# Display_EUA.net
KiCad netlist of a schematic drawn in Altium Designer
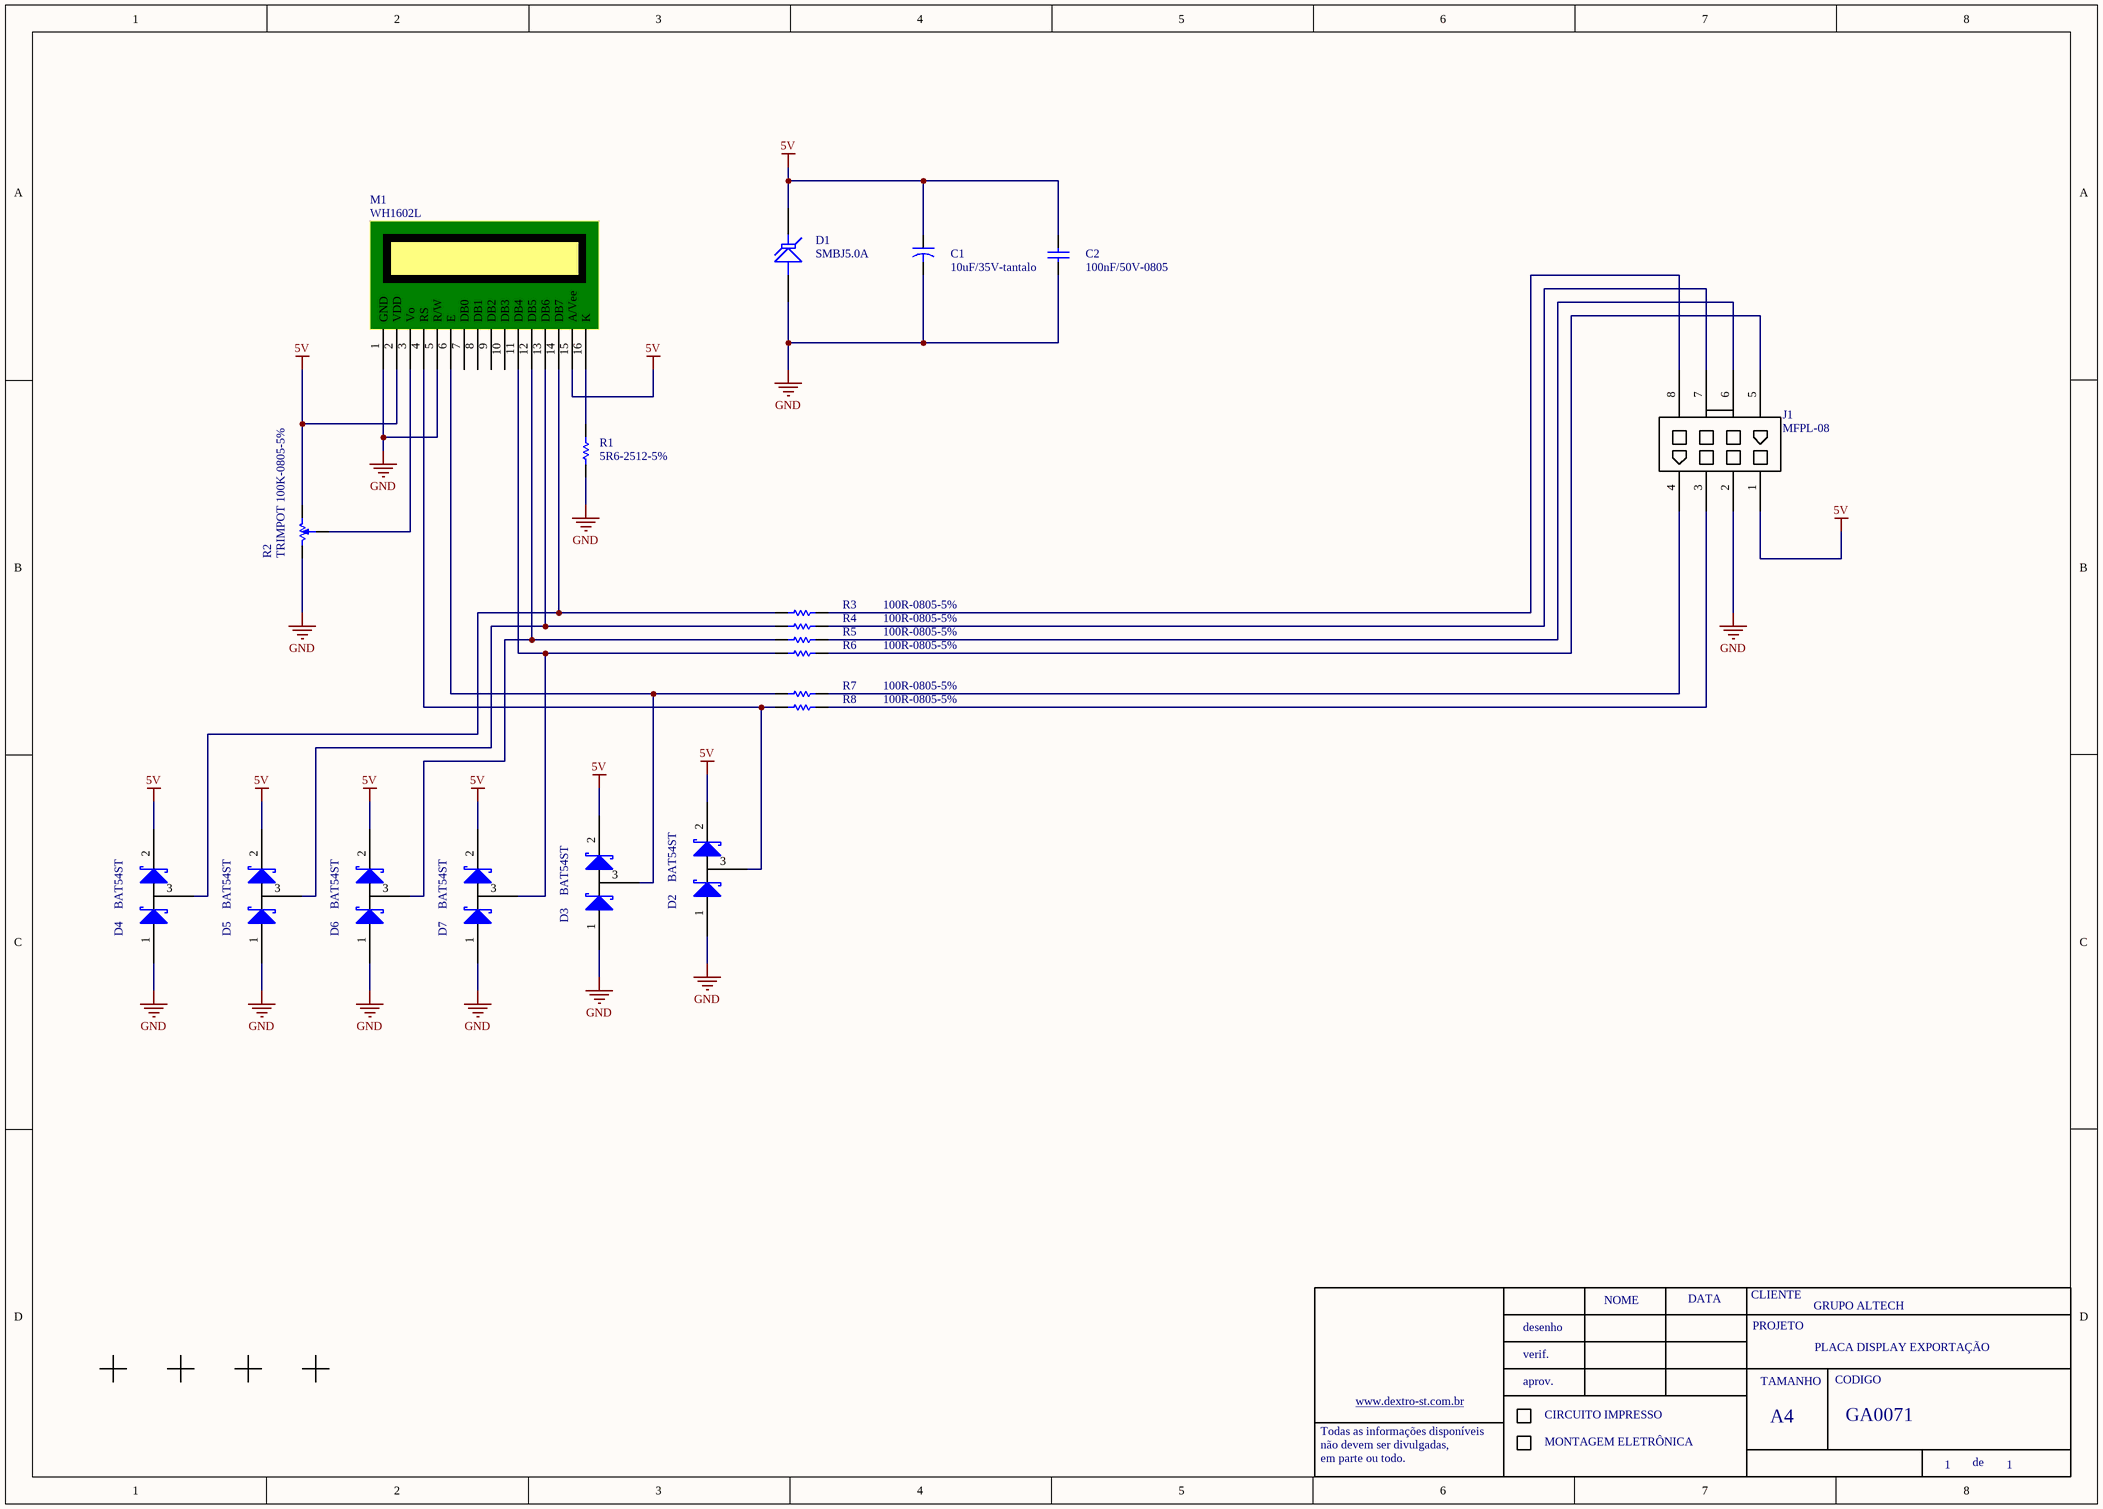
[diagram p0: Display_EUA.SchDoc]

(export (version "E")
  (design (tool "Eeschema 10.0.6"))
  (components
    (comp (ref "C1")
      (value "10uF/35V-tantalo")
      (footprint "tantalo vishay E")
      (libsource (lib "AquinoLib") (part "10uF/35V-tantalo"))
    )
    (comp (ref "C2")
      (value "100nF/50V-0805")
      (footprint "0805-REVISADO ONDA")
      (libsource (lib "AquinoLib") (part "100nF/50-0805-NPO"))
    )
    (comp (ref "D1")
      (value "SMBJ5.0A")
      (footprint "DO-214AA")
      (libsource (lib "AquinoLib") (part "SMBJ5.0A"))
    )
    (comp (ref "D2")
      (value "BAT54ST")
      (footprint "SOT23 - REVISADO ONDA")
      (libsource (lib "AquinoLib") (part "BAT54ST"))
    )
    (comp (ref "D3")
      (value "BAT54ST")
      (footprint "SOT23 - REVISADO ONDA")
      (libsource (lib "AquinoLib") (part "BAT54ST"))
    )
    (comp (ref "D4")
      (value "BAT54ST")
      (footprint "SOT23 - REVISADO ONDA")
      (libsource (lib "AquinoLib") (part "BAT54ST"))
    )
    (comp (ref "D5")
      (value "BAT54ST")
      (footprint "SOT23 - REVISADO ONDA")
      (libsource (lib "AquinoLib") (part "BAT54ST"))
    )
    (comp (ref "D6")
      (value "BAT54ST")
      (footprint "SOT23 - REVISADO ONDA")
      (libsource (lib "AquinoLib") (part "BAT54ST"))
    )
    (comp (ref "D7")
      (value "BAT54ST")
      (footprint "SOT23 - REVISADO ONDA")
      (libsource (lib "AquinoLib") (part "BAT54ST"))
    )
    (comp (ref "FD1")
      (value "FID")
      (footprint "FIDUCIAL CRUZ")
      (libsource (lib "ChaveDigital3") (part "FIDUCIAL"))
    )
    (comp (ref "FD2")
      (value "FID")
      (footprint "FIDUCIAL CRUZ")
      (libsource (lib "ChaveDigital3") (part "FIDUCIAL"))
    )
    (comp (ref "FD3")
      (value "FID")
      (footprint "FIDUCIAL CRUZ")
      (libsource (lib "ChaveDigital3") (part "FIDUCIAL"))
    )
    (comp (ref "FD4")
      (value "FID")
      (footprint "FIDUCIAL CRUZ")
      (libsource (lib "ChaveDigital3") (part "FIDUCIAL"))
    )
    (comp (ref "J1") (value "MFPL-08") (footprint "MFPC-08") (libsource (lib "AquinoLib") (part "MFPL-08")))
    (comp (ref "M1") (value "WH1602L") (footprint "WH1602L1") (libsource (lib "AquinoLib") (part "WH1602L")))
    (comp (ref "R1")
      (value "5R6-2512-5%")
      (footprint "2512 - REVISADO ONDA")
      (libsource (lib "AquinoLib") (part "5R6-2512-1%"))
    )
    (comp (ref "R2")
      (value "TRIMPOT 100K-0805-5%")
      (footprint "trimmer 3386")
      (libsource (lib "AquinoLib") (part "TRIMPOT 10K-3386"))
    )
    (comp (ref "R3")
      (value "100R-0805-5%")
      (footprint "0805-REVISADO ONDA")
      (libsource (lib "AquinoLib") (part "100R-0805-5%"))
    )
    (comp (ref "R4")
      (value "100R-0805-5%")
      (footprint "0805-REVISADO ONDA")
      (libsource (lib "AquinoLib") (part "100R-0805-5%"))
    )
    (comp (ref "R5")
      (value "100R-0805-5%")
      (footprint "0805-REVISADO ONDA")
      (libsource (lib "AquinoLib") (part "100R-0805-5%"))
    )
    (comp (ref "R6")
      (value "100R-0805-5%")
      (footprint "0805-REVISADO ONDA")
      (libsource (lib "AquinoLib") (part "100R-0805-5%"))
    )
    (comp (ref "R7")
      (value "100R-0805-5%")
      (footprint "0805-REVISADO ONDA")
      (libsource (lib "AquinoLib") (part "100R-0805-5%"))
    )
    (comp (ref "R8")
      (value "100R-0805-5%")
      (footprint "0805-REVISADO ONDA")
      (libsource (lib "AquinoLib") (part "100R-0805-5%"))
    )
  )
  (nets
    (net (code "1") (name "5V") (class "Default")
      (node (ref "C1") (pin "1") (pinfunction "1_1") (pintype "passive"))
      (node (ref "C2") (pin "2") (pinfunction "2_2") (pintype "passive"))
      (node (ref "D1") (pin "2") (pinfunction "K_2") (pintype "passive"))
      (node (ref "D2") (pin "2") (pinfunction "2_2") (pintype "passive"))
      (node (ref "D3") (pin "2") (pinfunction "2_2") (pintype "passive"))
      (node (ref "D4") (pin "2") (pinfunction "2_2") (pintype "passive"))
      (node (ref "D5") (pin "2") (pinfunction "2_2") (pintype "passive"))
      (node (ref "D6") (pin "2") (pinfunction "2_2") (pintype "passive"))
      (node (ref "D7") (pin "2") (pinfunction "2_2") (pintype "passive"))
      (node (ref "J1") (pin "1") (pinfunction "1_1") (pintype "passive"))
      (node (ref "M1") (pin "15") (pinfunction "A/Vee_15") (pintype "passive"))
      (node (ref "M1") (pin "2") (pinfunction "VDD_2") (pintype "passive"))
      (node (ref "R2") (pin "3") (pinfunction "3_3") (pintype "passive"))
    )
    (net (code "2") (name "GND") (class "Default")
      (node (ref "C1") (pin "2") (pinfunction "2_2") (pintype "passive"))
      (node (ref "C2") (pin "1") (pinfunction "1_1") (pintype "passive"))
      (node (ref "D1") (pin "1") (pinfunction "A_1") (pintype "passive"))
      (node (ref "D2") (pin "1") (pinfunction "1_1") (pintype "passive"))
      (node (ref "D3") (pin "1") (pinfunction "1_1") (pintype "passive"))
      (node (ref "D4") (pin "1") (pinfunction "1_1") (pintype "passive"))
      (node (ref "D5") (pin "1") (pinfunction "1_1") (pintype "passive"))
      (node (ref "D6") (pin "1") (pinfunction "1_1") (pintype "passive"))
      (node (ref "D7") (pin "1") (pinfunction "1_1") (pintype "passive"))
      (node (ref "J1") (pin "2") (pinfunction "2_2") (pintype "passive"))
      (node (ref "M1") (pin "1") (pinfunction "GND_1") (pintype "passive"))
      (node (ref "M1") (pin "5") (pinfunction "R/W_5") (pintype "passive"))
      (node (ref "R1") (pin "1") (pinfunction "1_1") (pintype "passive"))
      (node (ref "R2") (pin "1") (pinfunction "1_1") (pintype "passive"))
    )
    (net (code "3") (name "Net-(J1-Pad3)") (class "Default")
      (node (ref "J1") (pin "3") (pinfunction "3_3") (pintype "passive"))
      (node (ref "R8") (pin "2") (pinfunction "2_2") (pintype "passive"))
    )
    (net (code "4") (name "Net-(J1-Pad4)") (class "Default")
      (node (ref "J1") (pin "4") (pinfunction "4_4") (pintype "passive"))
      (node (ref "R7") (pin "2") (pinfunction "2_2") (pintype "passive"))
    )
    (net (code "5") (name "Net-(J1-Pad5)") (class "Default")
      (node (ref "J1") (pin "5") (pinfunction "5_5") (pintype "passive"))
      (node (ref "R6") (pin "2") (pinfunction "2_2") (pintype "passive"))
    )
    (net (code "6") (name "Net-(J1-Pad6)") (class "Default")
      (node (ref "J1") (pin "6") (pinfunction "6_6") (pintype "passive"))
      (node (ref "R5") (pin "2") (pinfunction "2_2") (pintype "passive"))
    )
    (net (code "7") (name "Net-(J1-Pad7)") (class "Default")
      (node (ref "J1") (pin "7") (pinfunction "7_7") (pintype "passive"))
      (node (ref "R4") (pin "2") (pinfunction "2_2") (pintype "passive"))
    )
    (net (code "8") (name "Net-(J1-Pad8)") (class "Default")
      (node (ref "J1") (pin "8") (pinfunction "8_8") (pintype "passive"))
      (node (ref "R3") (pin "2") (pinfunction "2_2") (pintype "passive"))
    )
    (net (code "9") (name "Net-(M1-DB4)") (class "Default")
      (node (ref "D7") (pin "3") (pinfunction "3_3") (pintype "passive"))
      (node (ref "M1") (pin "11") (pinfunction "DB4_11") (pintype "passive"))
      (node (ref "R6") (pin "1") (pinfunction "1_1") (pintype "passive"))
    )
    (net (code "10") (name "Net-(M1-DB5)") (class "Default")
      (node (ref "D6") (pin "3") (pinfunction "3_3") (pintype "passive"))
      (node (ref "M1") (pin "12") (pinfunction "DB5_12") (pintype "passive"))
      (node (ref "R5") (pin "1") (pinfunction "1_1") (pintype "passive"))
    )
    (net (code "11") (name "Net-(M1-DB6)") (class "Default")
      (node (ref "D5") (pin "3") (pinfunction "3_3") (pintype "passive"))
      (node (ref "M1") (pin "13") (pinfunction "DB6_13") (pintype "passive"))
      (node (ref "R4") (pin "1") (pinfunction "1_1") (pintype "passive"))
    )
    (net (code "12") (name "Net-(M1-DB7)") (class "Default")
      (node (ref "D4") (pin "3") (pinfunction "3_3") (pintype "passive"))
      (node (ref "M1") (pin "14") (pinfunction "DB7_14") (pintype "passive"))
      (node (ref "R3") (pin "1") (pinfunction "1_1") (pintype "passive"))
    )
    (net (code "13") (name "Net-(M1-E)") (class "Default")
      (node (ref "D3") (pin "3") (pinfunction "3_3") (pintype "passive"))
      (node (ref "M1") (pin "6") (pinfunction "E_6") (pintype "passive"))
      (node (ref "R7") (pin "1") (pinfunction "1_1") (pintype "passive"))
    )
    (net (code "14") (name "Net-(M1-K)") (class "Default")
      (node (ref "M1") (pin "16") (pinfunction "K_16") (pintype "passive"))
      (node (ref "R1") (pin "2") (pinfunction "2_2") (pintype "passive"))
    )
    (net (code "15") (name "Net-(M1-RS)") (class "Default")
      (node (ref "D2") (pin "3") (pinfunction "3_3") (pintype "passive"))
      (node (ref "M1") (pin "4") (pinfunction "RS_4") (pintype "passive"))
      (node (ref "R8") (pin "1") (pinfunction "1_1") (pintype "passive"))
    )
    (net (code "16") (name "Net-(M1-Vo)") (class "Default")
      (node (ref "M1") (pin "3") (pinfunction "Vo_3") (pintype "passive"))
      (node (ref "R2") (pin "2") (pinfunction "2_2") (pintype "passive"))
    )
    (net (code "17") (name "unconnected-(M1-DB0-Pad7)") (class "Default")
      (node (ref "M1") (pin "7") (pinfunction "DB0_7") (pintype "passive"))
    )
    (net (code "18") (name "unconnected-(M1-DB1-Pad8)") (class "Default")
      (node (ref "M1") (pin "8") (pinfunction "DB1_8") (pintype "passive"))
    )
    (net (code "19") (name "unconnected-(M1-DB2-Pad9)") (class "Default")
      (node (ref "M1") (pin "9") (pinfunction "DB2_9") (pintype "passive"))
    )
    (net (code "20") (name "unconnected-(M1-DB3-Pad10)") (class "Default")
      (node (ref "M1") (pin "10") (pinfunction "DB3_10") (pintype "passive"))
    )
  )
)
